# squematic.net
KiCad netlist of a schematic drawn in EAGLE
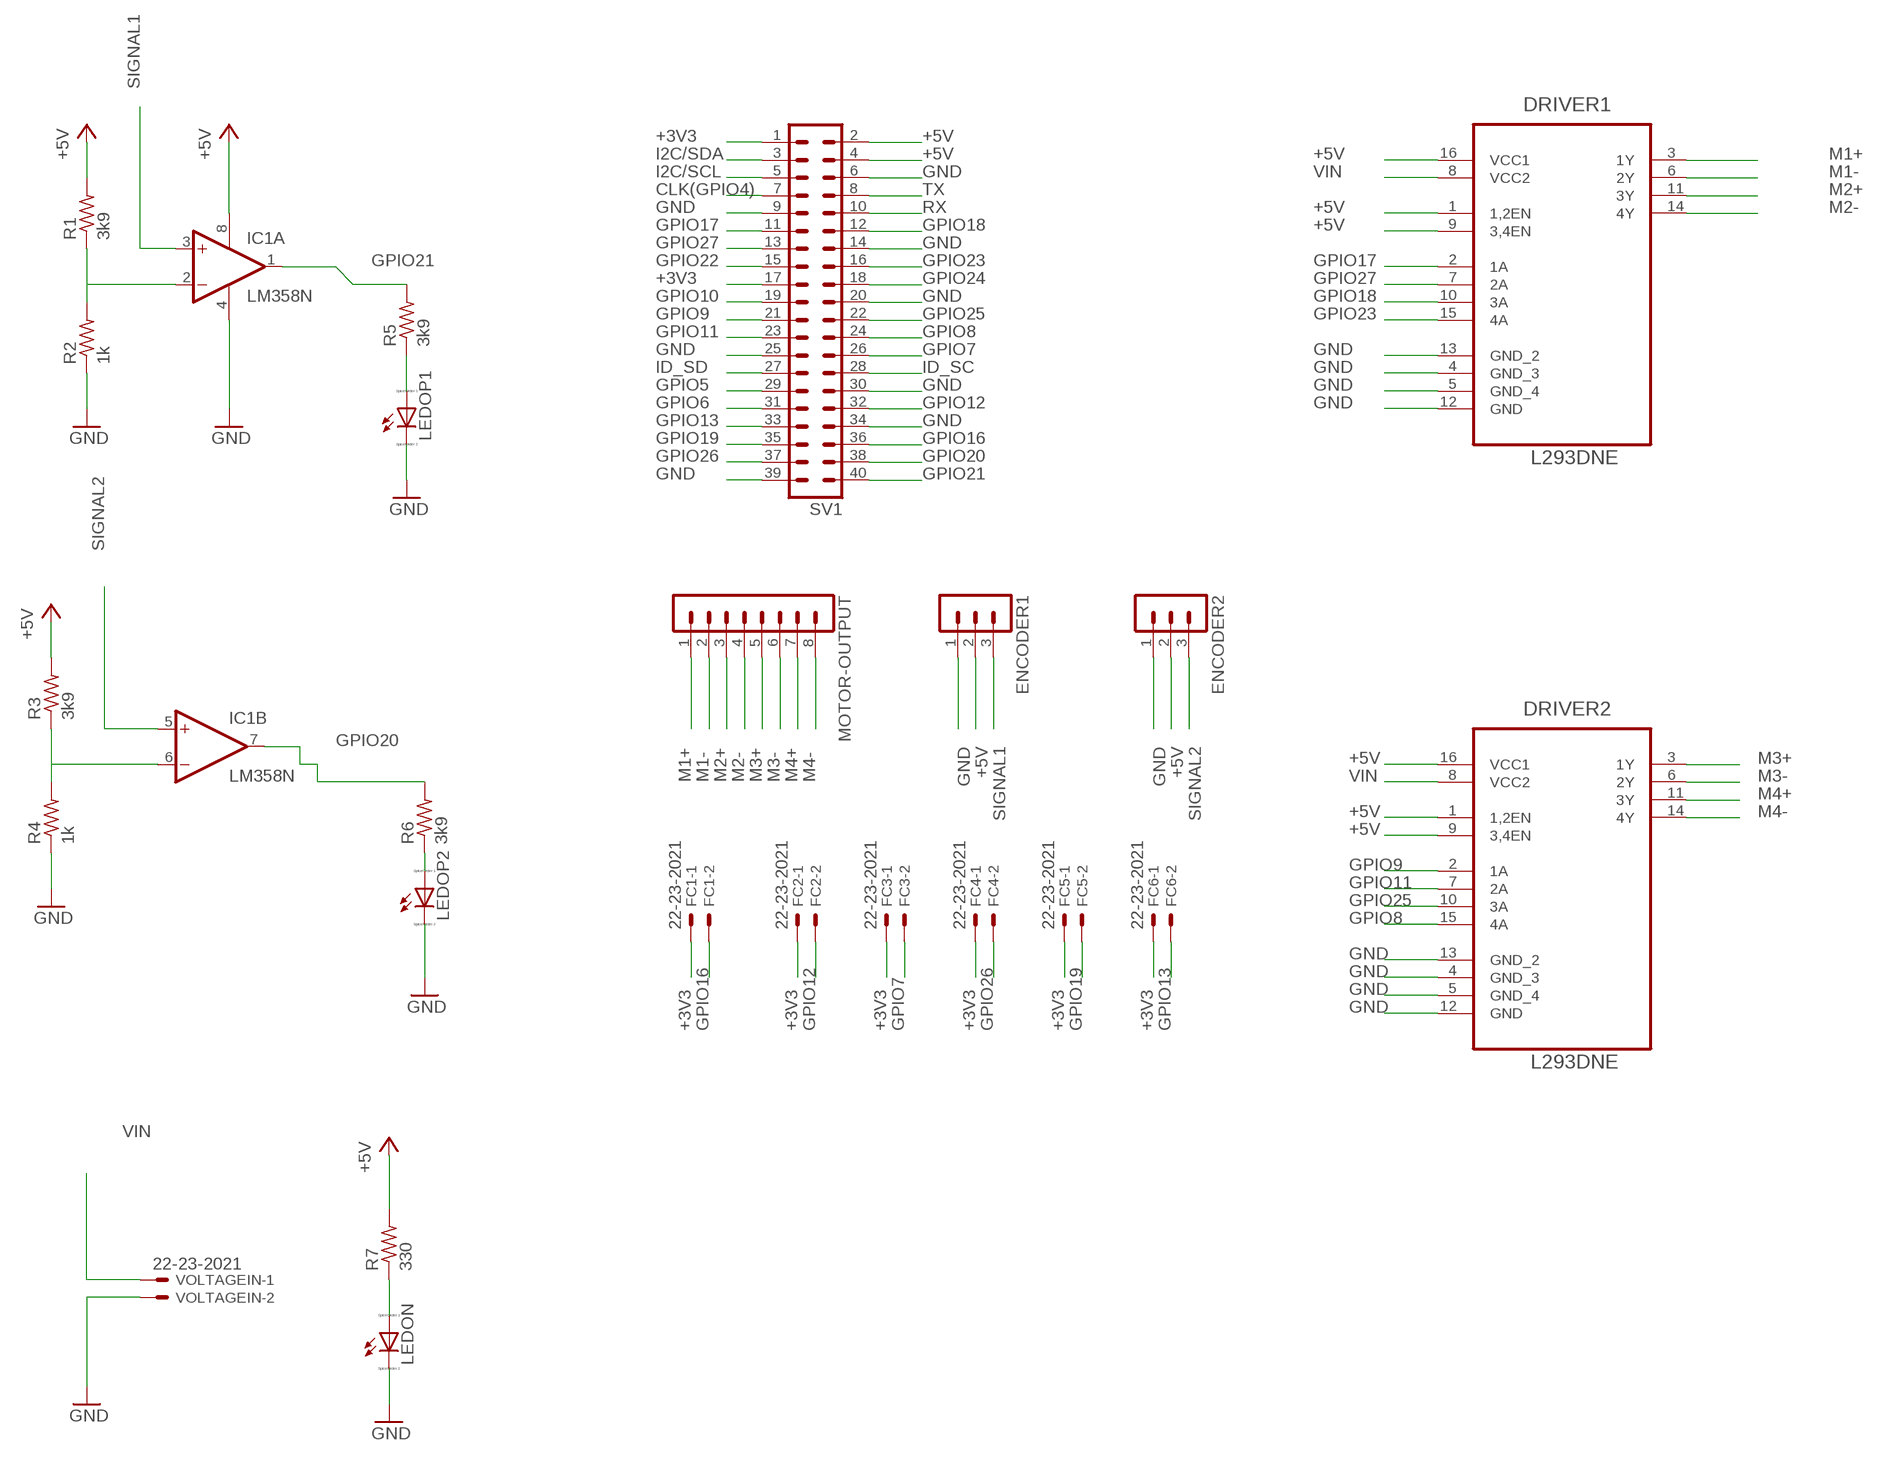
[diagram p0: schematic, sheet 1]

(export (version "E")
  (design (tool "Eeschema 10.0.6"))
  (components
    (comp (ref "DRIVER1")
      (value "L293DNE")
      (footprint "eagle-import:DIP254P762X508-16")
      (libsource (lib "eagle-import") (part "L293DNE"))
    )
    (comp (ref "DRIVER2")
      (value "L293DNE")
      (footprint "eagle-import:DIP254P762X508-16")
      (libsource (lib "eagle-import") (part "L293DNE"))
    )
    (comp (ref "ENCODER1")
      (value "MA03-1")
      (footprint "eagle-import:MA03-1")
      (libsource (lib "eagle-import") (part "MA03-1"))
    )
    (comp (ref "ENCODER2")
      (value "MA03-1")
      (footprint "eagle-import:MA03-1")
      (libsource (lib "eagle-import") (part "MA03-1"))
    )
    (comp (ref "FC1")
      (value "22-23-2021")
      (footprint "eagle-import:22-23-2021")
      (fields (field (name "MF") "MOLEX"))
      (libsource (lib "eagle-import") (part "22-23-2021"))
    )
    (comp (ref "FC2")
      (value "22-23-2021")
      (footprint "eagle-import:22-23-2021")
      (fields (field (name "MF") "MOLEX"))
      (libsource (lib "eagle-import") (part "22-23-2021"))
    )
    (comp (ref "FC3")
      (value "22-23-2021")
      (footprint "eagle-import:22-23-2021")
      (fields (field (name "MF") "MOLEX"))
      (libsource (lib "eagle-import") (part "22-23-2021"))
    )
    (comp (ref "FC4")
      (value "22-23-2021")
      (footprint "eagle-import:22-23-2021")
      (fields (field (name "MF") "MOLEX"))
      (libsource (lib "eagle-import") (part "22-23-2021"))
    )
    (comp (ref "FC5")
      (value "22-23-2021")
      (footprint "eagle-import:22-23-2021")
      (fields (field (name "MF") "MOLEX"))
      (libsource (lib "eagle-import") (part "22-23-2021"))
    )
    (comp (ref "FC6")
      (value "22-23-2021")
      (footprint "eagle-import:22-23-2021")
      (fields (field (name "MF") "MOLEX"))
      (libsource (lib "eagle-import") (part "22-23-2021"))
    )
    (comp (ref "IC1")
      (value "LM358N")
      (footprint "eagle-import:DIL08")
      (libsource (lib "eagle-import") (part "LM358N"))
    )
    (comp (ref "LEDON")
      (value "LED_ELD260")
      (footprint "eagle-import:LED_LD260")
      (libsource (lib "eagle-import") (part "LED_ELD260"))
    )
    (comp (ref "LEDOP1")
      (value "LED_ELD260")
      (footprint "eagle-import:LED_LD260")
      (libsource (lib "eagle-import") (part "LED_ELD260"))
    )
    (comp (ref "LEDOP2")
      (value "LED_ELD260")
      (footprint "eagle-import:LED_LD260")
      (libsource (lib "eagle-import") (part "LED_ELD260"))
    )
    (comp (ref "MOTOR-OUTPUT")
      (value "MA08-1")
      (footprint "eagle-import:MA08-1")
      (libsource (lib "eagle-import") (part "MA08-1"))
    )
    (comp (ref "R1")
      (value "3k9")
      (footprint "eagle-import:0207_10")
      (libsource (lib "eagle-import") (part "R-US_0207/10"))
    )
    (comp (ref "R2")
      (value "1k")
      (footprint "eagle-import:0207_10")
      (libsource (lib "eagle-import") (part "R-US_0207/10"))
    )
    (comp (ref "R3")
      (value "3k9")
      (footprint "eagle-import:0207_10")
      (libsource (lib "eagle-import") (part "R-US_0207/10"))
    )
    (comp (ref "R4")
      (value "1k")
      (footprint "eagle-import:0207_10")
      (libsource (lib "eagle-import") (part "R-US_0207/10"))
    )
    (comp (ref "R5")
      (value "3k9")
      (footprint "eagle-import:0207_10")
      (libsource (lib "eagle-import") (part "R-US_0207/10"))
    )
    (comp (ref "R6")
      (value "3k9")
      (footprint "eagle-import:0207_10")
      (libsource (lib "eagle-import") (part "R-US_0207/10"))
    )
    (comp (ref "R7")
      (value "330")
      (footprint "eagle-import:0207_10")
      (libsource (lib "eagle-import") (part "R-US_0207/10"))
    )
    (comp (ref "SV1")
      (value "MA20-2")
      (footprint "eagle-import:MA20-2")
      (libsource (lib "eagle-import") (part "MA20-2"))
    )
    (comp (ref "VOLTAGEIN")
      (value "22-23-2021")
      (footprint "eagle-import:22-23-2021")
      (fields (field (name "MF") "MOLEX"))
      (libsource (lib "eagle-import") (part "22-23-2021"))
    )
  )
  (nets
    (net (code "1") (name "+5V") (class "Default")
      (node (ref "DRIVER1") (pin "1") (pinfunction "1,2EN_1") (pintype "input"))
      (node (ref "DRIVER1") (pin "16") (pinfunction "VCC1_16") (pintype "power_in"))
      (node (ref "DRIVER1") (pin "9") (pinfunction "3,4EN_9") (pintype "input"))
      (node (ref "DRIVER2") (pin "1") (pinfunction "1,2EN_1") (pintype "input"))
      (node (ref "DRIVER2") (pin "16") (pinfunction "VCC1_16") (pintype "power_in"))
      (node (ref "DRIVER2") (pin "9") (pinfunction "3,4EN_9") (pintype "input"))
      (node (ref "ENCODER1") (pin "2") (pinfunction "2_2") (pintype "passive"))
      (node (ref "ENCODER2") (pin "2") (pinfunction "2_2") (pintype "passive"))
      (node (ref "IC1") (pin "8") (pinfunction "V+_8") (pintype "power_in"))
      (node (ref "R1") (pin "2") (pinfunction "2_2") (pintype "passive"))
      (node (ref "R3") (pin "2") (pinfunction "2_2") (pintype "passive"))
      (node (ref "R7") (pin "2") (pinfunction "2_2") (pintype "passive"))
      (node (ref "SV1") (pin "2") (pinfunction "2_2") (pintype "passive"))
      (node (ref "SV1") (pin "4") (pinfunction "4_4") (pintype "passive"))
    )
    (net (code "2") (name "/+3V3") (class "Default")
      (node (ref "FC1") (pin "1") (pinfunction "S_1") (pintype "passive"))
      (node (ref "FC2") (pin "1") (pinfunction "S_1") (pintype "passive"))
      (node (ref "FC3") (pin "1") (pinfunction "S_1") (pintype "passive"))
      (node (ref "FC4") (pin "1") (pinfunction "S_1") (pintype "passive"))
      (node (ref "FC5") (pin "1") (pinfunction "S_1") (pintype "passive"))
      (node (ref "FC6") (pin "1") (pinfunction "S_1") (pintype "passive"))
      (node (ref "SV1") (pin "1") (pinfunction "1_1") (pintype "passive"))
      (node (ref "SV1") (pin "17") (pinfunction "17_17") (pintype "passive"))
    )
    (net (code "3") (name "/CLK(GPIO4)") (class "Default")
      (node (ref "SV1") (pin "7") (pinfunction "7_7") (pintype "passive"))
    )
    (net (code "4") (name "/GPIO5") (class "Default")
      (node (ref "SV1") (pin "29") (pinfunction "29_29") (pintype "passive"))
    )
    (net (code "5") (name "/GPIO6") (class "Default")
      (node (ref "SV1") (pin "31") (pinfunction "31_31") (pintype "passive"))
    )
    (net (code "6") (name "/GPIO7") (class "Default")
      (node (ref "FC3") (pin "2") (pinfunction "S_2") (pintype "passive"))
      (node (ref "SV1") (pin "26") (pinfunction "26_26") (pintype "passive"))
    )
    (net (code "7") (name "/GPIO8") (class "Default")
      (node (ref "DRIVER2") (pin "15") (pinfunction "4A_15") (pintype "input"))
      (node (ref "SV1") (pin "24") (pinfunction "24_24") (pintype "passive"))
    )
    (net (code "8") (name "/GPIO9") (class "Default")
      (node (ref "DRIVER2") (pin "2") (pinfunction "1A_2") (pintype "input"))
      (node (ref "SV1") (pin "21") (pinfunction "21_21") (pintype "passive"))
    )
    (net (code "9") (name "/GPIO10") (class "Default")
      (node (ref "SV1") (pin "19") (pinfunction "19_19") (pintype "passive"))
    )
    (net (code "10") (name "/GPIO11") (class "Default")
      (node (ref "DRIVER2") (pin "7") (pinfunction "2A_7") (pintype "input"))
      (node (ref "SV1") (pin "23") (pinfunction "23_23") (pintype "passive"))
    )
    (net (code "11") (name "/GPIO12") (class "Default")
      (node (ref "FC2") (pin "2") (pinfunction "S_2") (pintype "passive"))
      (node (ref "SV1") (pin "32") (pinfunction "32_32") (pintype "passive"))
    )
    (net (code "12") (name "/GPIO13") (class "Default")
      (node (ref "FC6") (pin "2") (pinfunction "S_2") (pintype "passive"))
      (node (ref "SV1") (pin "33") (pinfunction "33_33") (pintype "passive"))
    )
    (net (code "13") (name "/GPIO16") (class "Default")
      (node (ref "FC1") (pin "2") (pinfunction "S_2") (pintype "passive"))
      (node (ref "SV1") (pin "36") (pinfunction "36_36") (pintype "passive"))
    )
    (net (code "14") (name "/GPIO17") (class "Default")
      (node (ref "DRIVER1") (pin "2") (pinfunction "1A_2") (pintype "input"))
      (node (ref "SV1") (pin "11") (pinfunction "11_11") (pintype "passive"))
    )
    (net (code "15") (name "/GPIO18") (class "Default")
      (node (ref "DRIVER1") (pin "10") (pinfunction "3A_10") (pintype "input"))
      (node (ref "SV1") (pin "12") (pinfunction "12_12") (pintype "passive"))
    )
    (net (code "16") (name "/GPIO19") (class "Default")
      (node (ref "FC5") (pin "2") (pinfunction "S_2") (pintype "passive"))
      (node (ref "SV1") (pin "35") (pinfunction "35_35") (pintype "passive"))
    )
    (net (code "17") (name "/GPIO20") (class "Default")
      (node (ref "IC1") (pin "7") (pinfunction "OUT_7") (pintype "output"))
      (node (ref "R6") (pin "2") (pinfunction "2_2") (pintype "passive"))
      (node (ref "SV1") (pin "38") (pinfunction "38_38") (pintype "passive"))
    )
    (net (code "18") (name "/GPIO21") (class "Default")
      (node (ref "IC1") (pin "1") (pinfunction "OUT_1") (pintype "output"))
      (node (ref "R5") (pin "2") (pinfunction "2_2") (pintype "passive"))
      (node (ref "SV1") (pin "40") (pinfunction "40_40") (pintype "passive"))
    )
    (net (code "19") (name "/GPIO22") (class "Default")
      (node (ref "SV1") (pin "15") (pinfunction "15_15") (pintype "passive"))
    )
    (net (code "20") (name "/GPIO23") (class "Default")
      (node (ref "DRIVER1") (pin "15") (pinfunction "4A_15") (pintype "input"))
      (node (ref "SV1") (pin "16") (pinfunction "16_16") (pintype "passive"))
    )
    (net (code "21") (name "/GPIO24") (class "Default")
      (node (ref "SV1") (pin "18") (pinfunction "18_18") (pintype "passive"))
    )
    (net (code "22") (name "/GPIO25") (class "Default")
      (node (ref "DRIVER2") (pin "10") (pinfunction "3A_10") (pintype "input"))
      (node (ref "SV1") (pin "22") (pinfunction "22_22") (pintype "passive"))
    )
    (net (code "23") (name "/GPIO26") (class "Default")
      (node (ref "FC4") (pin "2") (pinfunction "S_2") (pintype "passive"))
      (node (ref "SV1") (pin "37") (pinfunction "37_37") (pintype "passive"))
    )
    (net (code "24") (name "/GPIO27") (class "Default")
      (node (ref "DRIVER1") (pin "7") (pinfunction "2A_7") (pintype "input"))
      (node (ref "SV1") (pin "13") (pinfunction "13_13") (pintype "passive"))
    )
    (net (code "25") (name "/I2C{slash}SCL") (class "Default")
      (node (ref "SV1") (pin "5") (pinfunction "5_5") (pintype "passive"))
    )
    (net (code "26") (name "/I2C{slash}SDA") (class "Default")
      (node (ref "SV1") (pin "3") (pinfunction "3_3") (pintype "passive"))
    )
    (net (code "27") (name "/ID_SC") (class "Default")
      (node (ref "SV1") (pin "28") (pinfunction "28_28") (pintype "passive"))
    )
    (net (code "28") (name "/ID_SD") (class "Default")
      (node (ref "SV1") (pin "27") (pinfunction "27_27") (pintype "passive"))
    )
    (net (code "29") (name "/M1+") (class "Default")
      (node (ref "DRIVER1") (pin "3") (pinfunction "1Y_3") (pintype "output"))
      (node (ref "MOTOR-OUTPUT") (pin "1") (pinfunction "1_1") (pintype "passive"))
    )
    (net (code "30") (name "/M1-") (class "Default")
      (node (ref "DRIVER1") (pin "6") (pinfunction "2Y_6") (pintype "output"))
      (node (ref "MOTOR-OUTPUT") (pin "2") (pinfunction "2_2") (pintype "passive"))
    )
    (net (code "31") (name "/M2+") (class "Default")
      (node (ref "DRIVER1") (pin "11") (pinfunction "3Y_11") (pintype "output"))
      (node (ref "MOTOR-OUTPUT") (pin "3") (pinfunction "3_3") (pintype "passive"))
    )
    (net (code "32") (name "/M2-") (class "Default")
      (node (ref "DRIVER1") (pin "14") (pinfunction "4Y_14") (pintype "output"))
      (node (ref "MOTOR-OUTPUT") (pin "4") (pinfunction "4_4") (pintype "passive"))
    )
    (net (code "33") (name "/M3+") (class "Default")
      (node (ref "DRIVER2") (pin "3") (pinfunction "1Y_3") (pintype "output"))
      (node (ref "MOTOR-OUTPUT") (pin "5") (pinfunction "5_5") (pintype "passive"))
    )
    (net (code "34") (name "/M3-") (class "Default")
      (node (ref "DRIVER2") (pin "6") (pinfunction "2Y_6") (pintype "output"))
      (node (ref "MOTOR-OUTPUT") (pin "6") (pinfunction "6_6") (pintype "passive"))
    )
    (net (code "35") (name "/M4+") (class "Default")
      (node (ref "DRIVER2") (pin "11") (pinfunction "3Y_11") (pintype "output"))
      (node (ref "MOTOR-OUTPUT") (pin "7") (pinfunction "7_7") (pintype "passive"))
    )
    (net (code "36") (name "/M4-") (class "Default")
      (node (ref "DRIVER2") (pin "14") (pinfunction "4Y_14") (pintype "output"))
      (node (ref "MOTOR-OUTPUT") (pin "8") (pinfunction "8_8") (pintype "passive"))
    )
    (net (code "37") (name "/RX") (class "Default")
      (node (ref "SV1") (pin "10") (pinfunction "10_10") (pintype "passive"))
    )
    (net (code "38") (name "/SIGNAL1") (class "Default")
      (node (ref "ENCODER1") (pin "3") (pinfunction "3_3") (pintype "passive"))
      (node (ref "IC1") (pin "3") (pinfunction "+IN_3") (pintype "input"))
    )
    (net (code "39") (name "/SIGNAL2") (class "Default")
      (node (ref "ENCODER2") (pin "3") (pinfunction "3_3") (pintype "passive"))
      (node (ref "IC1") (pin "5") (pinfunction "+IN_5") (pintype "input"))
    )
    (net (code "40") (name "/TX") (class "Default")
      (node (ref "SV1") (pin "8") (pinfunction "8_8") (pintype "passive"))
    )
    (net (code "41") (name "/VIN") (class "Default")
      (node (ref "DRIVER1") (pin "8") (pinfunction "VCC2_8") (pintype "power_in"))
      (node (ref "DRIVER2") (pin "8") (pinfunction "VCC2_8") (pintype "power_in"))
      (node (ref "VOLTAGEIN") (pin "1") (pinfunction "S_1") (pintype "passive"))
    )
    (net (code "42") (name "GND") (class "Default")
      (node (ref "DRIVER1") (pin "12") (pinfunction "GND_12") (pintype "passive"))
      (node (ref "DRIVER1") (pin "13") (pinfunction "GND_2_13") (pintype "passive"))
      (node (ref "DRIVER1") (pin "4") (pinfunction "GND_3_4") (pintype "passive"))
      (node (ref "DRIVER1") (pin "5") (pinfunction "GND_4_5") (pintype "passive"))
      (node (ref "DRIVER2") (pin "12") (pinfunction "GND_12") (pintype "passive"))
      (node (ref "DRIVER2") (pin "13") (pinfunction "GND_2_13") (pintype "passive"))
      (node (ref "DRIVER2") (pin "4") (pinfunction "GND_3_4") (pintype "passive"))
      (node (ref "DRIVER2") (pin "5") (pinfunction "GND_4_5") (pintype "passive"))
      (node (ref "ENCODER1") (pin "1") (pinfunction "1_1") (pintype "passive"))
      (node (ref "ENCODER2") (pin "1") (pinfunction "1_1") (pintype "passive"))
      (node (ref "IC1") (pin "4") (pinfunction "V-_4") (pintype "power_in"))
      (node (ref "LEDON") (pin "K") (pinfunction "C_K") (pintype "passive"))
      (node (ref "LEDOP1") (pin "K") (pinfunction "C_K") (pintype "passive"))
      (node (ref "LEDOP2") (pin "K") (pinfunction "C_K") (pintype "passive"))
      (node (ref "R2") (pin "1") (pinfunction "1_1") (pintype "passive"))
      (node (ref "R4") (pin "1") (pinfunction "1_1") (pintype "passive"))
      (node (ref "SV1") (pin "14") (pinfunction "14_14") (pintype "passive"))
      (node (ref "SV1") (pin "20") (pinfunction "20_20") (pintype "passive"))
      (node (ref "SV1") (pin "25") (pinfunction "25_25") (pintype "passive"))
      (node (ref "SV1") (pin "30") (pinfunction "30_30") (pintype "passive"))
      (node (ref "SV1") (pin "34") (pinfunction "34_34") (pintype "passive"))
      (node (ref "SV1") (pin "39") (pinfunction "39_39") (pintype "passive"))
      (node (ref "SV1") (pin "6") (pinfunction "6_6") (pintype "passive"))
      (node (ref "SV1") (pin "9") (pinfunction "9_9") (pintype "passive"))
      (node (ref "VOLTAGEIN") (pin "2") (pinfunction "S_2") (pintype "passive"))
    )
    (net (code "43") (name "Net-(IC1A--IN)") (class "Default")
      (node (ref "IC1") (pin "2") (pinfunction "-IN_2") (pintype "input"))
      (node (ref "R1") (pin "1") (pinfunction "1_1") (pintype "passive"))
      (node (ref "R2") (pin "2") (pinfunction "2_2") (pintype "passive"))
    )
    (net (code "44") (name "Net-(IC1B--IN)") (class "Default")
      (node (ref "IC1") (pin "6") (pinfunction "-IN_6") (pintype "input"))
      (node (ref "R3") (pin "1") (pinfunction "1_1") (pintype "passive"))
      (node (ref "R4") (pin "2") (pinfunction "2_2") (pintype "passive"))
    )
    (net (code "45") (name "Net-(LEDON-PadA)") (class "Default")
      (node (ref "LEDON") (pin "A") (pinfunction "A_A") (pintype "passive"))
      (node (ref "R7") (pin "1") (pinfunction "1_1") (pintype "passive"))
    )
    (net (code "46") (name "Net-(LEDOP1-PadA)") (class "Default")
      (node (ref "LEDOP1") (pin "A") (pinfunction "A_A") (pintype "passive"))
      (node (ref "R5") (pin "1") (pinfunction "1_1") (pintype "passive"))
    )
    (net (code "47") (name "Net-(LEDOP2-PadA)") (class "Default")
      (node (ref "LEDOP2") (pin "A") (pinfunction "A_A") (pintype "passive"))
      (node (ref "R6") (pin "1") (pinfunction "1_1") (pintype "passive"))
    )
  )
)
